# PPG_Foot_Module.net
KiCad netlist of a schematic drawn in EasyEDA
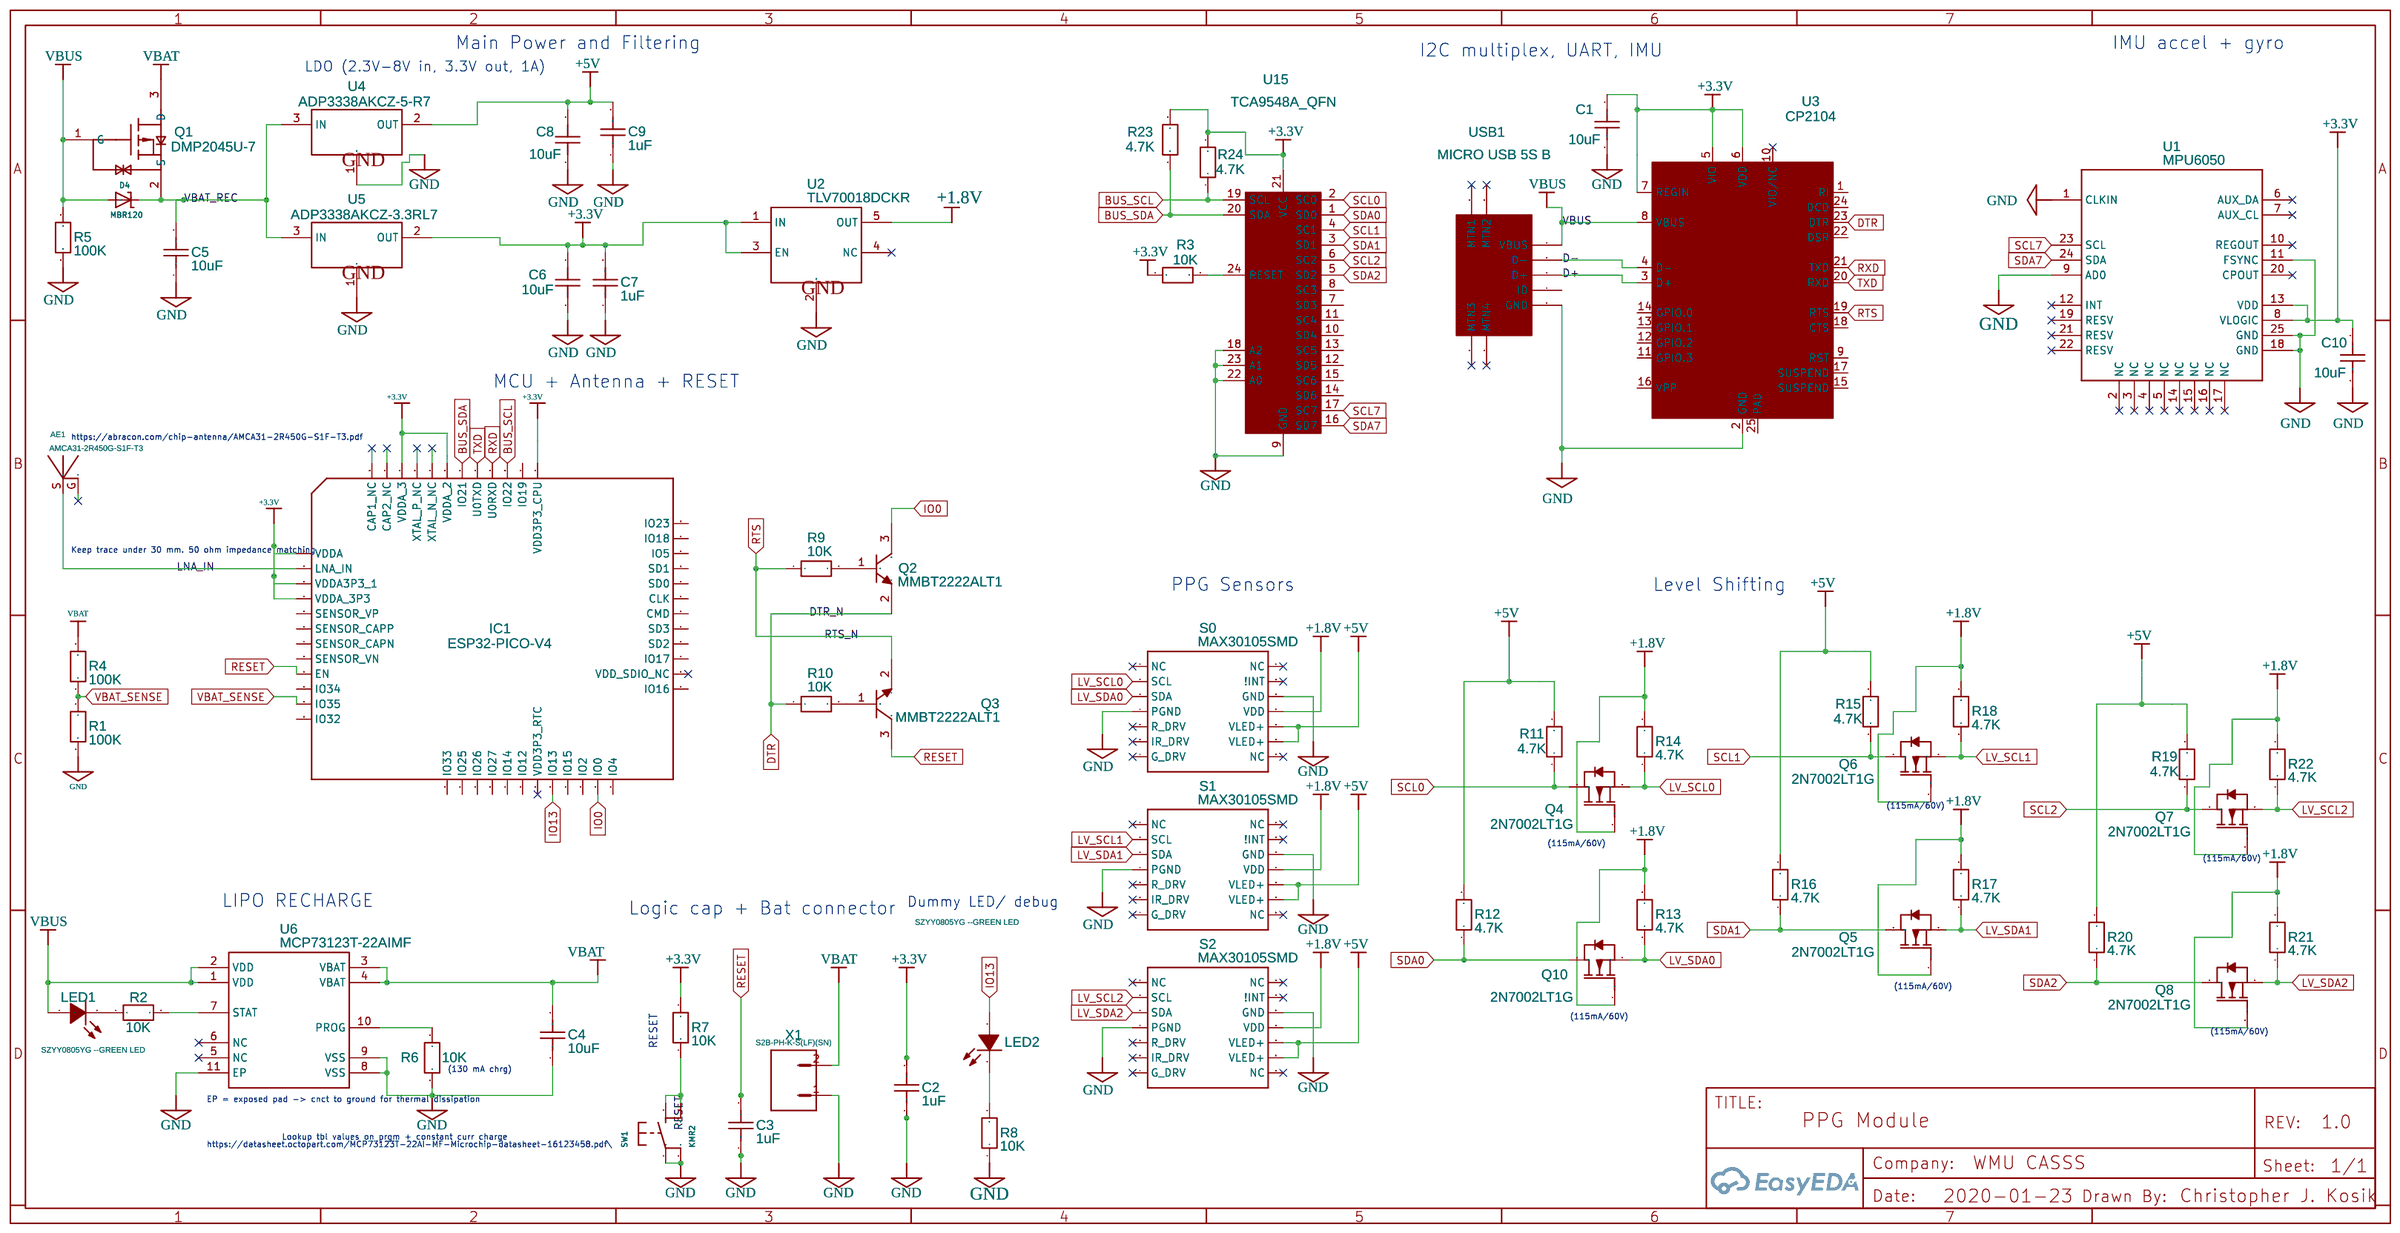
[diagram p0: schematic sheet]

(export (version "E")
  (design (tool "Eeschema 10.0.6"))
  (components
    (comp (ref "AE1")
      (value "AMCA31-2R450G-S1F-T3")
      (fields (field (name "BOM_Supplier Part") "535-14095-1-ND"))
      (libsource (lib "") (part "AMCA31-2R450G-S1F-T3"))
    )
    (comp (ref "C1")
      (value "10uF")
      (fields
        (field (name "BOM_Manufacturer Part") "GJ821BR61E106KE11L")
        (field (name "BOM_Supplier Part") "C471371")
      )
      (libsource (lib "") (part "GJ821BR61E106KE11L_1"))
    )
    (comp (ref "C2")
      (value "1uF")
      (fields
        (field (name "BOM_Manufacturer Part") "C0402X5R105M6R3NT")
        (field (name "BOM_Supplier Part") "C475247")
      )
      (libsource (lib "") (part "C0402X5R105M6R3NT"))
    )
    (comp (ref "C3")
      (value "1uF")
      (fields
        (field (name "BOM_Manufacturer Part") "C0402X5R105M6R3NT")
        (field (name "BOM_Supplier Part") "C475247")
      )
      (libsource (lib "") (part "C0402X5R105M6R3NT"))
    )
    (comp (ref "C4")
      (value "10uF")
      (fields
        (field (name "BOM_Manufacturer Part") "GJ821BR61E106KE11L")
        (field (name "BOM_Supplier Part") "C471371")
      )
      (libsource (lib "") (part "GJ821BR61E106KE11L"))
    )
    (comp (ref "C5")
      (value "10uF")
      (fields
        (field (name "BOM_Manufacturer Part") "GJ821BR61E106KE11L")
        (field (name "BOM_Supplier Part") "C471371")
      )
      (libsource (lib "") (part "GJ821BR61E106KE11L"))
    )
    (comp (ref "C6")
      (value "10uF")
      (fields
        (field (name "BOM_Manufacturer Part") "GJ821BR61E106KE11L")
        (field (name "BOM_Supplier Part") "C471371")
      )
      (libsource (lib "") (part "GJ821BR61E106KE11L_1"))
    )
    (comp (ref "C7")
      (value "1uF")
      (fields
        (field (name "BOM_Manufacturer Part") "C0402X5R105M6R3NT")
        (field (name "BOM_Supplier Part") "C475247")
      )
      (libsource (lib "") (part "C0402X5R105M6R3NT"))
    )
    (comp (ref "C8")
      (value "10uF")
      (fields
        (field (name "BOM_Manufacturer Part") "GJ821BR61E106KE11L")
        (field (name "BOM_Supplier Part") "C471371")
      )
      (libsource (lib "") (part "GJ821BR61E106KE11L"))
    )
    (comp (ref "C9")
      (value "1uF")
      (fields
        (field (name "BOM_Manufacturer Part") "C0402X5R105M6R3NT")
        (field (name "BOM_Supplier Part") "C475247")
      )
      (libsource (lib "") (part "C0402X5R105M6R3NT"))
    )
    (comp (ref "C10")
      (value "10uF")
      (fields
        (field (name "BOM_Manufacturer Part") "GJ821BR61E106KE11L")
        (field (name "BOM_Supplier Part") "C471371")
      )
      (libsource (lib "") (part "GJ821BR61E106KE11L_1"))
    )
    (comp (ref "D4") (value "MBR120") (libsource (lib "") (part "Unknown_75_-680")))
    (comp (ref "IC1") (value "ESP32-PICO-V4") (libsource (lib "") (part "CY8C29666_QFN48")))
    (comp (ref "LED1")
      (value "SZYY0805YG --GREEN LED")
      (fields
        (field (name "BOM_Manufacturer Part") "SZYY0805YG")
        (field (name "BOM_Supplier Part") "C434435")
      )
      (libsource (lib "") (part "SZYY0805YG --GREEN LED"))
    )
    (comp (ref "LED2")
      (value "SZYY0805YG --GREEN LED")
      (fields
        (field (name "BOM_Manufacturer Part") "SZYY0805YG")
        (field (name "BOM_Supplier Part") "C434435")
      )
      (libsource (lib "") (part "SZYY0805YG --GREEN LED_1"))
    )
    (comp (ref "Q1")
      (value "DMP2045U-7")
      (fields (field (name "BOM_Supplier Part") "C146276"))
      (libsource (lib "") (part "DMP2045U-7"))
    )
    (comp (ref "Q2") (value "MMBT2222ALT1") (libsource (lib "") (part "MMBT2222ALT1")))
    (comp (ref "Q3") (value "MMBT2222ALT1") (libsource (lib "") (part "MMBT2222ALT1_1")))
    (comp (ref "Q4")
      (value "2N7002LT1G")
      (fields (field (name "BOM_Supplier Part") "C16338"))
      (libsource (lib "") (part "2N7002LT1G"))
    )
    (comp (ref "Q5")
      (value "2N7002LT1G")
      (fields (field (name "BOM_Supplier Part") "C16338"))
      (libsource (lib "") (part "2N7002LT1G"))
    )
    (comp (ref "Q6")
      (value "2N7002LT1G")
      (fields (field (name "BOM_Supplier Part") "C16338"))
      (libsource (lib "") (part "2N7002LT1G"))
    )
    (comp (ref "Q7")
      (value "2N7002LT1G")
      (fields (field (name "BOM_Supplier Part") "C16338"))
      (libsource (lib "") (part "2N7002LT1G"))
    )
    (comp (ref "Q8")
      (value "2N7002LT1G")
      (fields (field (name "BOM_Supplier Part") "C16338"))
      (libsource (lib "") (part "2N7002LT1G"))
    )
    (comp (ref "Q10")
      (value "2N7002LT1G")
      (fields (field (name "BOM_Supplier Part") "C16338"))
      (libsource (lib "") (part "2N7002LT1G"))
    )
    (comp (ref "R1")
      (value "100K")
      (fields
        (field (name "BOM_Manufacturer Part") "RAT031003FTP")
        (field (name "BOM_Supplier Part") "C304472")
      )
      (libsource (lib "") (part "RAT031003FTP --100K"))
    )
    (comp (ref "R2")
      (value "10K")
      (fields
        (field (name "BOM_Manufacturer Part") "CR-03JA7---10K")
        (field (name "BOM_Supplier Part") "C465463")
      )
      (libsource (lib "") (part "CR-03JA7---10K"))
    )
    (comp (ref "R3")
      (value "10K")
      (fields
        (field (name "BOM_Manufacturer Part") "CR-03JA7---10K")
        (field (name "BOM_Supplier Part") "C465463")
      )
      (libsource (lib "") (part "CR-03JA7---10K"))
    )
    (comp (ref "R4")
      (value "100K")
      (fields
        (field (name "BOM_Manufacturer Part") "RAT031003FTP")
        (field (name "BOM_Supplier Part") "C304472")
      )
      (libsource (lib "") (part "RAT031003FTP --100K"))
    )
    (comp (ref "R5")
      (value "100K")
      (fields
        (field (name "BOM_Manufacturer Part") "RAT031003FTP")
        (field (name "BOM_Supplier Part") "C304472")
      )
      (libsource (lib "") (part "RAT031003FTP --100K"))
    )
    (comp (ref "R6")
      (value "10K")
      (fields
        (field (name "BOM_Manufacturer Part") "CR-03JA7---10K")
        (field (name "BOM_Supplier Part") "C465463")
      )
      (libsource (lib "") (part "CR-03JA7---10K_1"))
    )
    (comp (ref "R7")
      (value "10K")
      (fields
        (field (name "BOM_Manufacturer Part") "CR-03JA7---10K")
        (field (name "BOM_Supplier Part") "C465463")
      )
      (libsource (lib "") (part "CR-03JA7---10K_1"))
    )
    (comp (ref "R8")
      (value "10K")
      (fields
        (field (name "BOM_Manufacturer Part") "CR-03JA7---10K")
        (field (name "BOM_Supplier Part") "C465463")
      )
      (libsource (lib "") (part "CR-03JA7---10K_1"))
    )
    (comp (ref "R9")
      (value "10K")
      (fields
        (field (name "BOM_Manufacturer Part") "CR-03JA7---10K")
        (field (name "BOM_Supplier Part") "C465463")
      )
      (libsource (lib "") (part "CR-03JA7---10K"))
    )
    (comp (ref "R10")
      (value "10K")
      (fields
        (field (name "BOM_Manufacturer Part") "CR-03JA7---10K")
        (field (name "BOM_Supplier Part") "C465463")
      )
      (libsource (lib "") (part "CR-03JA7---10K"))
    )
    (comp (ref "R11")
      (value "4.7K")
      (fields
        (field (name "BOM_Manufacturer Part") "ERJP03J472V")
        (field (name "BOM_Supplier Part") "C427275")
      )
      (libsource (lib "") (part "ERJP03J472V --4.7K"))
    )
    (comp (ref "R12")
      (value "4.7K")
      (fields
        (field (name "BOM_Manufacturer Part") "ERJP03J472V")
        (field (name "BOM_Supplier Part") "C427275")
      )
      (libsource (lib "") (part "ERJP03J472V --4.7K"))
    )
    (comp (ref "R13")
      (value "4.7K")
      (fields
        (field (name "BOM_Manufacturer Part") "ERJP03J472V")
        (field (name "BOM_Supplier Part") "C427275")
      )
      (libsource (lib "") (part "ERJP03J472V --4.7K"))
    )
    (comp (ref "R14")
      (value "4.7K")
      (fields
        (field (name "BOM_Manufacturer Part") "ERJP03J472V")
        (field (name "BOM_Supplier Part") "C427275")
      )
      (libsource (lib "") (part "ERJP03J472V --4.7K"))
    )
    (comp (ref "R15")
      (value "4.7K")
      (fields
        (field (name "BOM_Manufacturer Part") "ERJP03J472V")
        (field (name "BOM_Supplier Part") "C427275")
      )
      (libsource (lib "") (part "ERJP03J472V --4.7K"))
    )
    (comp (ref "R16")
      (value "4.7K")
      (fields
        (field (name "BOM_Manufacturer Part") "ERJP03J472V")
        (field (name "BOM_Supplier Part") "C427275")
      )
      (libsource (lib "") (part "ERJP03J472V --4.7K"))
    )
    (comp (ref "R17")
      (value "4.7K")
      (fields
        (field (name "BOM_Manufacturer Part") "ERJP03J472V")
        (field (name "BOM_Supplier Part") "C427275")
      )
      (libsource (lib "") (part "ERJP03J472V --4.7K"))
    )
    (comp (ref "R18")
      (value "4.7K")
      (fields
        (field (name "BOM_Manufacturer Part") "ERJP03J472V")
        (field (name "BOM_Supplier Part") "C427275")
      )
      (libsource (lib "") (part "ERJP03J472V --4.7K"))
    )
    (comp (ref "R19")
      (value "4.7K")
      (fields
        (field (name "BOM_Manufacturer Part") "ERJP03J472V")
        (field (name "BOM_Supplier Part") "C427275")
      )
      (libsource (lib "") (part "ERJP03J472V --4.7K"))
    )
    (comp (ref "R20")
      (value "4.7K")
      (fields
        (field (name "BOM_Manufacturer Part") "ERJP03J472V")
        (field (name "BOM_Supplier Part") "C427275")
      )
      (libsource (lib "") (part "ERJP03J472V --4.7K"))
    )
    (comp (ref "R21")
      (value "4.7K")
      (fields
        (field (name "BOM_Manufacturer Part") "ERJP03J472V")
        (field (name "BOM_Supplier Part") "C427275")
      )
      (libsource (lib "") (part "ERJP03J472V --4.7K"))
    )
    (comp (ref "R22")
      (value "4.7K")
      (fields
        (field (name "BOM_Manufacturer Part") "ERJP03J472V")
        (field (name "BOM_Supplier Part") "C427275")
      )
      (libsource (lib "") (part "ERJP03J472V --4.7K"))
    )
    (comp (ref "R23")
      (value "4.7K")
      (fields
        (field (name "BOM_Manufacturer Part") "ERJP03J472V")
        (field (name "BOM_Supplier Part") "C427275")
      )
      (libsource (lib "") (part "ERJP03J472V --4.7K"))
    )
    (comp (ref "R24")
      (value "4.7K")
      (fields
        (field (name "BOM_Manufacturer Part") "ERJP03J472V")
        (field (name "BOM_Supplier Part") "C427275")
      )
      (libsource (lib "") (part "ERJP03J472V --4.7K"))
    )
    (comp (ref "S0") (value "MAX30105SMD") (libsource (lib "") (part "MAX30105SMD")))
    (comp (ref "S1") (value "MAX30105SMD") (libsource (lib "") (part "MAX30105SMD")))
    (comp (ref "S2") (value "MAX30105SMD") (libsource (lib "") (part "MAX30105SMD")))
    (comp (ref "SW1") (value "KMR2") (libsource (lib "") (part "Unknown_435_-60")))
    (comp (ref "U1") (value "MPU6050") (libsource (lib "") (part "MPU6050")))
    (comp (ref "U2") (value "TLV70018DCKR") (libsource (lib "") (part "TLV70018DCKR")))
    (comp (ref "U3") (value "CP2104") (libsource (lib "") (part "CP2104")))
    (comp (ref "U4") (value "ADP3338AKCZ-5-R7") (libsource (lib "") (part "ADP3338AKCZ-5-R7")))
    (comp (ref "U5") (value "ADP3338AKCZ-3.3RL7") (libsource (lib "") (part "ADP3338AKCZ-3.3RL7")))
    (comp (ref "U6") (value "MCP73123T-22AIMF") (libsource (lib "") (part "MCP73123T-22AIMF")))
    (comp (ref "U15") (value "TCA9548A_QFN") (libsource (lib "") (part "TCA9548A_QFN")))
    (comp (ref "USB1")
      (value "MICRO USB 5S B")
      (fields
        (field (name "BOM_Manufacturer Part") "micro USBFemale")
        (field (name "BOM_Supplier Part") "C10418")
      )
      (libsource (lib "") (part "MICRO USB 5S B"))
    )
    (comp (ref "X1") (value "S2B-PH-K-S(LF)(SN)") (libsource (lib "") (part "S2B-PH-K-S(LF)(SN)")))
  )
  (nets
    (net (code "1") (name "+1.8V") (class "Default")
      (node (ref "Q10") (pin "1") (pinfunction "G_1") (pintype "unspecified"))
      (node (ref "Q4") (pin "1") (pinfunction "G_1") (pintype "unspecified"))
      (node (ref "Q5") (pin "1") (pinfunction "G_1") (pintype "unspecified"))
      (node (ref "Q6") (pin "1") (pinfunction "G_1") (pintype "unspecified"))
      (node (ref "Q7") (pin "1") (pinfunction "G_1") (pintype "unspecified"))
      (node (ref "Q8") (pin "1") (pinfunction "G_1") (pintype "unspecified"))
      (node (ref "R13") (pin "2") (pinfunction "2_2") (pintype "unspecified"))
      (node (ref "R14") (pin "2") (pinfunction "2_2") (pintype "unspecified"))
      (node (ref "R17") (pin "2") (pinfunction "2_2") (pintype "unspecified"))
      (node (ref "R18") (pin "2") (pinfunction "2_2") (pintype "unspecified"))
      (node (ref "R21") (pin "2") (pinfunction "2_2") (pintype "unspecified"))
      (node (ref "R22") (pin "2") (pinfunction "2_2") (pintype "unspecified"))
      (node (ref "S0") (pin "11") (pinfunction "VDD_11") (pintype "bidirectional"))
      (node (ref "S1") (pin "11") (pinfunction "VDD_11") (pintype "bidirectional"))
      (node (ref "S2") (pin "11") (pinfunction "VDD_11") (pintype "bidirectional"))
      (node (ref "U2") (pin "5") (pinfunction "OUT_5") (pintype "passive"))
    )
    (net (code "2") (name "+3.3V") (class "Default")
      (node (ref "C1") (pin "1") (pinfunction "1_1") (pintype "unspecified"))
      (node (ref "C10") (pin "1") (pinfunction "1_1") (pintype "unspecified"))
      (node (ref "C2") (pin "2") (pinfunction "2_2") (pintype "unspecified"))
      (node (ref "C6") (pin "1") (pinfunction "1_1") (pintype "unspecified"))
      (node (ref "C7") (pin "2") (pinfunction "2_2") (pintype "unspecified"))
      (node (ref "IC1") (pin "1") (pinfunction "VDDA_1") (pintype "bidirectional"))
      (node (ref "IC1") (pin "3") (pinfunction "VDDA3P3_1_3") (pintype "bidirectional"))
      (node (ref "IC1") (pin "37") (pinfunction "VDD3P3_CPU_37") (pintype "bidirectional"))
      (node (ref "IC1") (pin "4") (pinfunction "VDDA_3P3_4") (pintype "bidirectional"))
      (node (ref "IC1") (pin "43") (pinfunction "VDDA_2_43") (pintype "bidirectional"))
      (node (ref "IC1") (pin "46") (pinfunction "VDDA_3_46") (pintype "bidirectional"))
      (node (ref "R23") (pin "2") (pinfunction "2_2") (pintype "unspecified"))
      (node (ref "R24") (pin "2") (pinfunction "2_2") (pintype "unspecified"))
      (node (ref "R3") (pin "1") (pinfunction "1_1") (pintype "unspecified"))
      (node (ref "R7") (pin "2") (pinfunction "2_2") (pintype "unspecified"))
      (node (ref "U1") (pin "13") (pinfunction "VDD_13") (pintype "passive"))
      (node (ref "U1") (pin "8") (pinfunction "VLOGIC_8") (pintype "passive"))
      (node (ref "U15") (pin "21") (pinfunction "VCC_21") (pintype "bidirectional"))
      (node (ref "U2") (pin "1") (pinfunction "IN_1") (pintype "passive"))
      (node (ref "U2") (pin "3") (pinfunction "EN_3") (pintype "unspecified"))
      (node (ref "U3") (pin "5") (pinfunction "VIO_5") (pintype "bidirectional"))
      (node (ref "U3") (pin "6") (pinfunction "VDD_6") (pintype "bidirectional"))
      (node (ref "U3") (pin "7") (pinfunction "REGIN_7") (pintype "bidirectional"))
      (node (ref "U5") (pin "2") (pinfunction "OUT_2") (pintype "passive"))
    )
    (net (code "3") (name "+5V") (class "Default")
      (node (ref "C8") (pin "2") (pinfunction "2_2") (pintype "unspecified"))
      (node (ref "C9") (pin "2") (pinfunction "2_2") (pintype "unspecified"))
      (node (ref "R11") (pin "2") (pinfunction "2_2") (pintype "unspecified"))
      (node (ref "R12") (pin "2") (pinfunction "2_2") (pintype "unspecified"))
      (node (ref "R15") (pin "2") (pinfunction "2_2") (pintype "unspecified"))
      (node (ref "R16") (pin "2") (pinfunction "2_2") (pintype "unspecified"))
      (node (ref "R19") (pin "2") (pinfunction "2_2") (pintype "unspecified"))
      (node (ref "R20") (pin "2") (pinfunction "2_2") (pintype "unspecified"))
      (node (ref "S0") (pin "10") (pinfunction "VLED+_10") (pintype "bidirectional"))
      (node (ref "S0") (pin "9") (pinfunction "VLED+_9") (pintype "bidirectional"))
      (node (ref "S1") (pin "10") (pinfunction "VLED+_10") (pintype "bidirectional"))
      (node (ref "S1") (pin "9") (pinfunction "VLED+_9") (pintype "bidirectional"))
      (node (ref "S2") (pin "10") (pinfunction "VLED+_10") (pintype "bidirectional"))
      (node (ref "S2") (pin "9") (pinfunction "VLED+_9") (pintype "bidirectional"))
      (node (ref "U4") (pin "2") (pinfunction "OUT_2") (pintype "passive"))
    )
    (net (code "4") (name "/D+") (class "Default")
      (node (ref "U3") (pin "3") (pinfunction "D+_3") (pintype "bidirectional"))
      (node (ref "USB1") (pin "3") (pinfunction "D+_3") (pintype "input"))
    )
    (net (code "5") (name "/D-") (class "Default")
      (node (ref "U3") (pin "4") (pinfunction "D-_4") (pintype "bidirectional"))
      (node (ref "USB1") (pin "2") (pinfunction "D-_2") (pintype "input"))
    )
    (net (code "6") (name "/LNA_IN") (class "Default")
      (node (ref "AE1") (pin "S") (pinfunction "S_S") (pintype "unspecified"))
      (node (ref "IC1") (pin "2") (pinfunction "LNA_IN_2") (pintype "bidirectional"))
    )
    (net (code "7") (name "/VBAT_REC") (class "Default")
      (node (ref "C5") (pin "2") (pinfunction "2_2") (pintype "unspecified"))
      (node (ref "D4") (pin "2") (pinfunction "C_2") (pintype "bidirectional"))
      (node (ref "Q1") (pin "2") (pinfunction "S_2") (pintype "unspecified"))
      (node (ref "U4") (pin "3") (pinfunction "IN_3") (pintype "passive"))
      (node (ref "U5") (pin "3") (pinfunction "IN_3") (pintype "passive"))
    )
    (net (code "8") (name "BUS_SCL") (class "Default")
      (node (ref "IC1") (pin "39") (pinfunction "IO22_39") (pintype "bidirectional"))
      (node (ref "R24") (pin "1") (pinfunction "1_1") (pintype "unspecified"))
      (node (ref "U15") (pin "19") (pinfunction "SCL_19") (pintype "bidirectional"))
    )
    (net (code "9") (name "BUS_SDA") (class "Default")
      (node (ref "IC1") (pin "42") (pinfunction "IO21_42") (pintype "bidirectional"))
      (node (ref "R23") (pin "1") (pinfunction "1_1") (pintype "unspecified"))
      (node (ref "U15") (pin "20") (pinfunction "SDA_20") (pintype "bidirectional"))
    )
    (net (code "10") (name "DTR") (class "Default")
      (node (ref "Q2") (pin "2") (pinfunction "E_2") (pintype "unspecified"))
      (node (ref "R10") (pin "1") (pinfunction "1_1") (pintype "unspecified"))
      (node (ref "U3") (pin "23") (pinfunction "DTR_23") (pintype "output"))
    )
    (net (code "11") (name "GND") (class "Default")
      (node (ref "C1") (pin "2") (pinfunction "2_2") (pintype "unspecified"))
      (node (ref "C10") (pin "2") (pinfunction "2_2") (pintype "unspecified"))
      (node (ref "C2") (pin "1") (pinfunction "1_1") (pintype "unspecified"))
      (node (ref "C3") (pin "1") (pinfunction "1_1") (pintype "unspecified"))
      (node (ref "C4") (pin "1") (pinfunction "1_1") (pintype "unspecified"))
      (node (ref "C5") (pin "1") (pinfunction "1_1") (pintype "unspecified"))
      (node (ref "C6") (pin "2") (pinfunction "2_2") (pintype "unspecified"))
      (node (ref "C7") (pin "1") (pinfunction "1_1") (pintype "unspecified"))
      (node (ref "C8") (pin "1") (pinfunction "1_1") (pintype "unspecified"))
      (node (ref "C9") (pin "1") (pinfunction "1_1") (pintype "unspecified"))
      (node (ref "R1") (pin "1") (pinfunction "1_1") (pintype "unspecified"))
      (node (ref "R5") (pin "1") (pinfunction "1_1") (pintype "unspecified"))
      (node (ref "R6") (pin "1") (pinfunction "1_1") (pintype "unspecified"))
      (node (ref "R8") (pin "1") (pinfunction "1_1") (pintype "unspecified"))
      (node (ref "S0") (pin "12") (pinfunction "GND_12") (pintype "bidirectional"))
      (node (ref "S0") (pin "4") (pinfunction "PGND_4") (pintype "bidirectional"))
      (node (ref "S1") (pin "12") (pinfunction "GND_12") (pintype "bidirectional"))
      (node (ref "S1") (pin "4") (pinfunction "PGND_4") (pintype "bidirectional"))
      (node (ref "S2") (pin "12") (pinfunction "GND_12") (pintype "bidirectional"))
      (node (ref "S2") (pin "4") (pinfunction "PGND_4") (pintype "bidirectional"))
      (node (ref "SW1") (pin "A") (pinfunction "P_A") (pintype "bidirectional"))
      (node (ref "SW1") (pin "A'") (pinfunction "P1_A'") (pintype "bidirectional"))
      (node (ref "U1") (pin "1") (pinfunction "CLKIN_1") (pintype "input"))
      (node (ref "U1") (pin "11") (pinfunction "FSYNC_11") (pintype "input"))
      (node (ref "U1") (pin "18") (pinfunction "GND_18") (pintype "passive"))
      (node (ref "U1") (pin "25") (pinfunction "GND_25") (pintype "passive"))
      (node (ref "U1") (pin "9") (pinfunction "AD0_9") (pintype "input"))
      (node (ref "U15") (pin "18") (pinfunction "A2_18") (pintype "input"))
      (node (ref "U15") (pin "22") (pinfunction "A0_22") (pintype "input"))
      (node (ref "U15") (pin "23") (pinfunction "A1_23") (pintype "input"))
      (node (ref "U15") (pin "9") (pinfunction "GND_9") (pintype "bidirectional"))
      (node (ref "U2") (pin "2") (pinfunction "GND_2") (pintype "passive"))
      (node (ref "U3") (pin "2") (pinfunction "GND_2") (pintype "bidirectional"))
      (node (ref "U4") (pin "1") (pinfunction "GND_1") (pintype "passive"))
      (node (ref "U5") (pin "1") (pinfunction "GND_1") (pintype "passive"))
      (node (ref "U6") (pin "11") (pinfunction "EP_11") (pintype "passive"))
      (node (ref "U6") (pin "8") (pinfunction "VSS_8") (pintype "passive"))
      (node (ref "U6") (pin "9") (pinfunction "VSS_9") (pintype "passive"))
      (node (ref "USB1") (pin "5") (pinfunction "GND_5") (pintype "input"))
      (node (ref "X1") (pin "1") (pinfunction "1_1") (pintype "unspecified"))
    )
    (net (code "12") (name "IO0") (class "Default")
      (node (ref "IC1") (pin "23") (pinfunction "IO0_23") (pintype "bidirectional"))
      (node (ref "Q2") (pin "3") (pinfunction "C_3") (pintype "unspecified"))
    )
    (net (code "13") (name "IO13") (class "Default")
      (node (ref "IC1") (pin "20") (pinfunction "IO13_20") (pintype "bidirectional"))
      (node (ref "LED2") (pin "1") (pinfunction "+_1") (pintype "unspecified"))
    )
    (net (code "14") (name "LV_SCL0") (class "Default")
      (node (ref "Q4") (pin "2") (pinfunction "S_2") (pintype "unspecified"))
      (node (ref "R14") (pin "1") (pinfunction "1_1") (pintype "unspecified"))
      (node (ref "S0") (pin "2") (pinfunction "SCL_2") (pintype "bidirectional"))
    )
    (net (code "15") (name "LV_SCL1") (class "Default")
      (node (ref "Q6") (pin "2") (pinfunction "S_2") (pintype "unspecified"))
      (node (ref "R18") (pin "1") (pinfunction "1_1") (pintype "unspecified"))
      (node (ref "S1") (pin "2") (pinfunction "SCL_2") (pintype "bidirectional"))
    )
    (net (code "16") (name "LV_SCL2") (class "Default")
      (node (ref "Q7") (pin "2") (pinfunction "S_2") (pintype "unspecified"))
      (node (ref "R22") (pin "1") (pinfunction "1_1") (pintype "unspecified"))
      (node (ref "S2") (pin "2") (pinfunction "SCL_2") (pintype "bidirectional"))
    )
    (net (code "17") (name "LV_SDA0") (class "Default")
      (node (ref "Q10") (pin "2") (pinfunction "S_2") (pintype "unspecified"))
      (node (ref "R13") (pin "1") (pinfunction "1_1") (pintype "unspecified"))
      (node (ref "S0") (pin "3") (pinfunction "SDA_3") (pintype "bidirectional"))
    )
    (net (code "18") (name "LV_SDA1") (class "Default")
      (node (ref "Q5") (pin "2") (pinfunction "S_2") (pintype "unspecified"))
      (node (ref "R17") (pin "1") (pinfunction "1_1") (pintype "unspecified"))
      (node (ref "S1") (pin "3") (pinfunction "SDA_3") (pintype "bidirectional"))
    )
    (net (code "19") (name "LV_SDA2") (class "Default")
      (node (ref "Q8") (pin "2") (pinfunction "S_2") (pintype "unspecified"))
      (node (ref "R21") (pin "1") (pinfunction "1_1") (pintype "unspecified"))
      (node (ref "S2") (pin "3") (pinfunction "SDA_3") (pintype "bidirectional"))
    )
    (net (code "20") (name "Net-(LED1--)") (class "Default")
      (node (ref "LED1") (pin "2") (pinfunction "-_2") (pintype "unspecified"))
      (node (ref "R2") (pin "1") (pinfunction "1_1") (pintype "unspecified"))
    )
    (net (code "21") (name "Net-(LED2--)") (class "Default")
      (node (ref "LED2") (pin "2") (pinfunction "-_2") (pintype "unspecified"))
      (node (ref "R8") (pin "2") (pinfunction "2_2") (pintype "unspecified"))
    )
    (net (code "22") (name "Net-(Q2-B)") (class "Default")
      (node (ref "Q2") (pin "1") (pinfunction "B_1") (pintype "unspecified"))
      (node (ref "R9") (pin "2") (pinfunction "2_2") (pintype "unspecified"))
    )
    (net (code "23") (name "Net-(Q3-B)") (class "Default")
      (node (ref "Q3") (pin "1") (pinfunction "B_1") (pintype "unspecified"))
      (node (ref "R10") (pin "2") (pinfunction "2_2") (pintype "unspecified"))
    )
    (net (code "24") (name "Net-(U6-PROG)") (class "Default")
      (node (ref "R6") (pin "2") (pinfunction "2_2") (pintype "unspecified"))
      (node (ref "U6") (pin "10") (pinfunction "PROG_10") (pintype "unspecified"))
    )
    (net (code "25") (name "Net-(U6-STAT)") (class "Default")
      (node (ref "R2") (pin "2") (pinfunction "2_2") (pintype "unspecified"))
      (node (ref "U6") (pin "7") (pinfunction "STAT_7") (pintype "unspecified"))
    )
    (net (code "26") (name "Net-(U15-RESET)") (class "Default")
      (node (ref "R3") (pin "2") (pinfunction "2_2") (pintype "unspecified"))
      (node (ref "U15") (pin "24") (pinfunction "RESET_24") (pintype "input"))
    )
    (net (code "27") (name "RESET") (class "Default")
      (node (ref "C3") (pin "2") (pinfunction "2_2") (pintype "unspecified"))
      (node (ref "IC1") (pin "9") (pinfunction "EN_9") (pintype "bidirectional"))
      (node (ref "Q3") (pin "3") (pinfunction "C_3") (pintype "unspecified"))
      (node (ref "R7") (pin "1") (pinfunction "1_1") (pintype "unspecified"))
      (node (ref "SW1") (pin "B") (pinfunction "S_B") (pintype "bidirectional"))
      (node (ref "SW1") (pin "B'") (pinfunction "S1_B'") (pintype "bidirectional"))
    )
    (net (code "28") (name "RTS") (class "Default")
      (node (ref "Q3") (pin "2") (pinfunction "E_2") (pintype "unspecified"))
      (node (ref "R9") (pin "1") (pinfunction "1_1") (pintype "unspecified"))
      (node (ref "U3") (pin "19") (pinfunction "RTS_19") (pintype "output"))
    )
    (net (code "29") (name "RXD") (class "Default")
      (node (ref "IC1") (pin "40") (pinfunction "U0RXD_40") (pintype "bidirectional"))
      (node (ref "U3") (pin "21") (pinfunction "TXD_21") (pintype "output"))
    )
    (net (code "30") (name "SCL0") (class "Default")
      (node (ref "Q4") (pin "3") (pinfunction "D_3") (pintype "unspecified"))
      (node (ref "R11") (pin "1") (pinfunction "1_1") (pintype "unspecified"))
      (node (ref "U15") (pin "2") (pinfunction "SC0_2") (pintype "bidirectional"))
    )
    (net (code "31") (name "SCL1") (class "Default")
      (node (ref "Q6") (pin "3") (pinfunction "D_3") (pintype "unspecified"))
      (node (ref "R15") (pin "1") (pinfunction "1_1") (pintype "unspecified"))
      (node (ref "U15") (pin "4") (pinfunction "SC1_4") (pintype "bidirectional"))
    )
    (net (code "32") (name "SCL2") (class "Default")
      (node (ref "Q7") (pin "3") (pinfunction "D_3") (pintype "unspecified"))
      (node (ref "R19") (pin "1") (pinfunction "1_1") (pintype "unspecified"))
      (node (ref "U15") (pin "6") (pinfunction "SC2_6") (pintype "bidirectional"))
    )
    (net (code "33") (name "SCL7") (class "Default")
      (node (ref "U1") (pin "23") (pinfunction "SCL_23") (pintype "input"))
      (node (ref "U15") (pin "17") (pinfunction "SC7_17") (pintype "bidirectional"))
    )
    (net (code "34") (name "SDA0") (class "Default")
      (node (ref "Q10") (pin "3") (pinfunction "D_3") (pintype "unspecified"))
      (node (ref "R12") (pin "1") (pinfunction "1_1") (pintype "unspecified"))
      (node (ref "U15") (pin "1") (pinfunction "SD0_1") (pintype "bidirectional"))
    )
    (net (code "35") (name "SDA1") (class "Default")
      (node (ref "Q5") (pin "3") (pinfunction "D_3") (pintype "unspecified"))
      (node (ref "R16") (pin "1") (pinfunction "1_1") (pintype "unspecified"))
      (node (ref "U15") (pin "3") (pinfunction "SD1_3") (pintype "bidirectional"))
    )
    (net (code "36") (name "SDA2") (class "Default")
      (node (ref "Q8") (pin "3") (pinfunction "D_3") (pintype "unspecified"))
      (node (ref "R20") (pin "1") (pinfunction "1_1") (pintype "unspecified"))
      (node (ref "U15") (pin "5") (pinfunction "SD2_5") (pintype "bidirectional"))
    )
    (net (code "37") (name "SDA7") (class "Default")
      (node (ref "U1") (pin "24") (pinfunction "SDA_24") (pintype "unspecified"))
      (node (ref "U15") (pin "16") (pinfunction "SD7_16") (pintype "bidirectional"))
    )
    (net (code "38") (name "TXD") (class "Default")
      (node (ref "IC1") (pin "41") (pinfunction "U0TXD_41") (pintype "bidirectional"))
      (node (ref "U3") (pin "20") (pinfunction "RXD_20") (pintype "input"))
    )
    (net (code "39") (name "VBAT") (class "Default")
      (node (ref "C4") (pin "2") (pinfunction "2_2") (pintype "unspecified"))
      (node (ref "Q1") (pin "3") (pinfunction "D_3") (pintype "unspecified"))
      (node (ref "R4") (pin "2") (pinfunction "2_2") (pintype "unspecified"))
      (node (ref "U6") (pin "3") (pinfunction "VBAT_3") (pintype "passive"))
      (node (ref "U6") (pin "4") (pinfunction "VBAT_4") (pintype "passive"))
      (node (ref "X1") (pin "2") (pinfunction "2_2") (pintype "unspecified"))
    )
    (net (code "40") (name "VBAT_SENSE") (class "Default")
      (node (ref "IC1") (pin "11") (pinfunction "IO35_11") (pintype "bidirectional"))
      (node (ref "R1") (pin "2") (pinfunction "2_2") (pintype "unspecified"))
      (node (ref "R4") (pin "1") (pinfunction "1_1") (pintype "unspecified"))
    )
    (net (code "41") (name "VBUS") (class "Default")
      (node (ref "D4") (pin "1") (pinfunction "A_1") (pintype "bidirectional"))
      (node (ref "LED1") (pin "1") (pinfunction "+_1") (pintype "unspecified"))
      (node (ref "Q1") (pin "1") (pinfunction "G_1") (pintype "unspecified"))
      (node (ref "R5") (pin "2") (pinfunction "2_2") (pintype "unspecified"))
      (node (ref "U3") (pin "8") (pinfunction "VBUS_8") (pintype "input"))
      (node (ref "U6") (pin "1") (pinfunction "VDD_1") (pintype "passive"))
      (node (ref "U6") (pin "2") (pinfunction "VDD_2") (pintype "passive"))
      (node (ref "USB1") (pin "1") (pinfunction "VBUS_1") (pintype "input"))
    )
    (net (code "42") (name "unconnected-(AE1-PadG)") (class "Default")
      (node (ref "AE1") (pin "G") (pinfunction "G_G") (pintype "unspecified+no_connect"))
    )
    (net (code "43") (name "unconnected-(IC1-CAP1_NC-Pad48)") (class "Default")
      (node (ref "IC1") (pin "48") (pinfunction "CAP1_NC_48") (pintype "bidirectional+no_connect"))
    )
    (net (code "44") (name "unconnected-(IC1-CAP2_NC-Pad47)") (class "Default")
      (node (ref "IC1") (pin "47") (pinfunction "CAP2_NC_47") (pintype "bidirectional+no_connect"))
    )
    (net (code "45") (name "unconnected-(IC1-CLK-Pad31)") (class "Default")
      (node (ref "IC1") (pin "31") (pinfunction "CLK_31") (pintype "bidirectional"))
    )
    (net (code "46") (name "unconnected-(IC1-CMD-Pad30)") (class "Default")
      (node (ref "IC1") (pin "30") (pinfunction "CMD_30") (pintype "bidirectional"))
    )
    (net (code "47") (name "unconnected-(IC1-IO2-Pad22)") (class "Default")
      (node (ref "IC1") (pin "22") (pinfunction "IO2_22") (pintype "bidirectional"))
    )
    (net (code "48") (name "unconnected-(IC1-IO4-Pad24)") (class "Default")
      (node (ref "IC1") (pin "24") (pinfunction "IO4_24") (pintype "bidirectional"))
    )
    (net (code "49") (name "unconnected-(IC1-IO5-Pad34)") (class "Default")
      (node (ref "IC1") (pin "34") (pinfunction "IO5_34") (pintype "bidirectional"))
    )
    (net (code "50") (name "unconnected-(IC1-IO12-Pad18)") (class "Default")
      (node (ref "IC1") (pin "18") (pinfunction "IO12_18") (pintype "bidirectional"))
    )
    (net (code "51") (name "unconnected-(IC1-IO14-Pad17)") (class "Default")
      (node (ref "IC1") (pin "17") (pinfunction "IO14_17") (pintype "bidirectional"))
    )
    (net (code "52") (name "unconnected-(IC1-IO15-Pad21)") (class "Default")
      (node (ref "IC1") (pin "21") (pinfunction "IO15_21") (pintype "bidirectional"))
    )
    (net (code "53") (name "unconnected-(IC1-IO16-Pad25)") (class "Default")
      (node (ref "IC1") (pin "25") (pinfunction "IO16_25") (pintype "bidirectional"))
    )
    (net (code "54") (name "unconnected-(IC1-IO17-Pad27)") (class "Default")
      (node (ref "IC1") (pin "27") (pinfunction "IO17_27") (pintype "bidirectional"))
    )
    (net (code "55") (name "unconnected-(IC1-IO18-Pad35)") (class "Default")
      (node (ref "IC1") (pin "35") (pinfunction "IO18_35") (pintype "bidirectional"))
    )
    (net (code "56") (name "unconnected-(IC1-IO19-Pad38)") (class "Default")
      (node (ref "IC1") (pin "38") (pinfunction "IO19_38") (pintype "bidirectional"))
    )
    (net (code "57") (name "unconnected-(IC1-IO23-Pad36)") (class "Default")
      (node (ref "IC1") (pin "36") (pinfunction "IO23_36") (pintype "bidirectional"))
    )
    (net (code "58") (name "unconnected-(IC1-IO25-Pad14)") (class "Default")
      (node (ref "IC1") (pin "14") (pinfunction "IO25_14") (pintype "bidirectional"))
    )
    (net (code "59") (name "unconnected-(IC1-IO26-Pad15)") (class "Default")
      (node (ref "IC1") (pin "15") (pinfunction "IO26_15") (pintype "bidirectional"))
    )
    (net (code "60") (name "unconnected-(IC1-IO27-Pad16)") (class "Default")
      (node (ref "IC1") (pin "16") (pinfunction "IO27_16") (pintype "bidirectional"))
    )
    (net (code "61") (name "unconnected-(IC1-IO32-Pad12)") (class "Default")
      (node (ref "IC1") (pin "12") (pinfunction "IO32_12") (pintype "bidirectional"))
    )
    (net (code "62") (name "unconnected-(IC1-IO33-Pad13)") (class "Default")
      (node (ref "IC1") (pin "13") (pinfunction "IO33_13") (pintype "bidirectional"))
    )
    (net (code "63") (name "unconnected-(IC1-IO34-Pad10)") (class "Default")
      (node (ref "IC1") (pin "10") (pinfunction "IO34_10") (pintype "bidirectional"))
    )
    (net (code "64") (name "unconnected-(IC1-SD0-Pad32)") (class "Default")
      (node (ref "IC1") (pin "32") (pinfunction "SD0_32") (pintype "bidirectional"))
    )
    (net (code "65") (name "unconnected-(IC1-SD1-Pad33)") (class "Default")
      (node (ref "IC1") (pin "33") (pinfunction "SD1_33") (pintype "bidirectional"))
    )
    (net (code "66") (name "unconnected-(IC1-SD2-Pad28)") (class "Default")
      (node (ref "IC1") (pin "28") (pinfunction "SD2_28") (pintype "bidirectional"))
    )
    (net (code "67") (name "unconnected-(IC1-SD3-Pad29)") (class "Default")
      (node (ref "IC1") (pin "29") (pinfunction "SD3_29") (pintype "bidirectional"))
    )
    (net (code "68") (name "unconnected-(IC1-SENSOR_CAPN-Pad7)") (class "Default")
      (node (ref "IC1") (pin "7") (pinfunction "SENSOR_CAPN_7") (pintype "bidirectional"))
    )
    (net (code "69") (name "unconnected-(IC1-SENSOR_CAPP-Pad6)") (class "Default")
      (node (ref "IC1") (pin "6") (pinfunction "SENSOR_CAPP_6") (pintype "bidirectional"))
    )
    (net (code "70") (name "unconnected-(IC1-SENSOR_VN-Pad8)") (class "Default")
      (node (ref "IC1") (pin "8") (pinfunction "SENSOR_VN_8") (pintype "bidirectional"))
    )
    (net (code "71") (name "unconnected-(IC1-SENSOR_VP-Pad5)") (class "Default")
      (node (ref "IC1") (pin "5") (pinfunction "SENSOR_VP_5") (pintype "bidirectional"))
    )
    (net (code "72") (name "unconnected-(IC1-VDD3P3_RTC-Pad19)") (class "Default")
      (node (ref "IC1") (pin "19") (pinfunction "VDD3P3_RTC_19") (pintype "bidirectional+no_connect"))
    )
    (net (code "73") (name "unconnected-(IC1-VDD_SDIO_NC-Pad26)") (class "Default")
      (node (ref "IC1") (pin "26") (pinfunction "VDD_SDIO_NC_26") (pintype "bidirectional+no_connect"))
    )
    (net (code "74") (name "unconnected-(IC1-XTAL_N_NC-Pad44)") (class "Default")
      (node (ref "IC1") (pin "44") (pinfunction "XTAL_N_NC_44") (pintype "bidirectional+no_connect"))
    )
    (net (code "75") (name "unconnected-(IC1-XTAL_P_NC-Pad45)") (class "Default")
      (node (ref "IC1") (pin "45") (pinfunction "XTAL_P_NC_45") (pintype "bidirectional+no_connect"))
    )
    (net (code "76") (name "unconnected-(S0-!INT-Pad13)") (class "Default")
      (node (ref "S0") (pin "13") (pinfunction "!INT_13") (pintype "bidirectional+no_connect"))
    )
    (net (code "77") (name "unconnected-(S0-G_DRV-Pad7)") (class "Default")
      (node (ref "S0") (pin "7") (pinfunction "G_DRV_7") (pintype "bidirectional+no_connect"))
    )
    (net (code "78") (name "unconnected-(S0-IR_DRV-Pad6)") (class "Default")
      (node (ref "S0") (pin "6") (pinfunction "IR_DRV_6") (pintype "bidirectional+no_connect"))
    )
    (net (code "79") (name "unconnected-(S0-NC-Pad1)") (class "Default")
      (node (ref "S0") (pin "1") (pinfunction "NC_1") (pintype "bidirectional+no_connect"))
    )
    (net (code "80") (name "unconnected-(S0-NC-Pad8)") (class "Default")
      (node (ref "S0") (pin "8") (pinfunction "NC_8") (pintype "bidirectional+no_connect"))
    )
    (net (code "81") (name "unconnected-(S0-NC-Pad14)") (class "Default")
      (node (ref "S0") (pin "14") (pinfunction "NC_14") (pintype "bidirectional+no_connect"))
    )
    (net (code "82") (name "unconnected-(S0-R_DRV-Pad5)") (class "Default")
      (node (ref "S0") (pin "5") (pinfunction "R_DRV_5") (pintype "bidirectional+no_connect"))
    )
    (net (code "83") (name "unconnected-(S1-!INT-Pad13)") (class "Default")
      (node (ref "S1") (pin "13") (pinfunction "!INT_13") (pintype "bidirectional+no_connect"))
    )
    (net (code "84") (name "unconnected-(S1-G_DRV-Pad7)") (class "Default")
      (node (ref "S1") (pin "7") (pinfunction "G_DRV_7") (pintype "bidirectional+no_connect"))
    )
    (net (code "85") (name "unconnected-(S1-IR_DRV-Pad6)") (class "Default")
      (node (ref "S1") (pin "6") (pinfunction "IR_DRV_6") (pintype "bidirectional+no_connect"))
    )
    (net (code "86") (name "unconnected-(S1-NC-Pad1)") (class "Default")
      (node (ref "S1") (pin "1") (pinfunction "NC_1") (pintype "bidirectional+no_connect"))
    )
    (net (code "87") (name "unconnected-(S1-NC-Pad8)") (class "Default")
      (node (ref "S1") (pin "8") (pinfunction "NC_8") (pintype "bidirectional+no_connect"))
    )
    (net (code "88") (name "unconnected-(S1-NC-Pad14)") (class "Default")
      (node (ref "S1") (pin "14") (pinfunction "NC_14") (pintype "bidirectional+no_connect"))
    )
    (net (code "89") (name "unconnected-(S1-R_DRV-Pad5)") (class "Default")
      (node (ref "S1") (pin "5") (pinfunction "R_DRV_5") (pintype "bidirectional+no_connect"))
    )
    (net (code "90") (name "unconnected-(S2-!INT-Pad13)") (class "Default")
      (node (ref "S2") (pin "13") (pinfunction "!INT_13") (pintype "bidirectional+no_connect"))
    )
    (net (code "91") (name "unconnected-(S2-G_DRV-Pad7)") (class "Default")
      (node (ref "S2") (pin "7") (pinfunction "G_DRV_7") (pintype "bidirectional+no_connect"))
    )
    (net (code "92") (name "unconnected-(S2-IR_DRV-Pad6)") (class "Default")
      (node (ref "S2") (pin "6") (pinfunction "IR_DRV_6") (pintype "bidirectional+no_connect"))
    )
    (net (code "93") (name "unconnected-(S2-NC-Pad1)") (class "Default")
      (node (ref "S2") (pin "1") (pinfunction "NC_1") (pintype "bidirectional+no_connect"))
    )
    (net (code "94") (name "unconnected-(S2-NC-Pad8)") (class "Default")
      (node (ref "S2") (pin "8") (pinfunction "NC_8") (pintype "bidirectional+no_connect"))
    )
    (net (code "95") (name "unconnected-(S2-NC-Pad14)") (class "Default")
      (node (ref "S2") (pin "14") (pinfunction "NC_14") (pintype "bidirectional+no_connect"))
    )
    (net (code "96") (name "unconnected-(S2-R_DRV-Pad5)") (class "Default")
      (node (ref "S2") (pin "5") (pinfunction "R_DRV_5") (pintype "bidirectional+no_connect"))
    )
    (net (code "97") (name "unconnected-(U1-AUX_CL-Pad7)") (class "Default")
      (node (ref "U1") (pin "7") (pinfunction "AUX_CL_7") (pintype "unspecified+no_connect"))
    )
    (net (code "98") (name "unconnected-(U1-AUX_DA-Pad6)") (class "Default")
      (node (ref "U1") (pin "6") (pinfunction "AUX_DA_6") (pintype "unspecified+no_connect"))
    )
    (net (code "99") (name "unconnected-(U1-CPOUT-Pad20)") (class "Default")
      (node (ref "U1") (pin "20") (pinfunction "CPOUT_20") (pintype "output+no_connect"))
    )
    (net (code "100") (name "unconnected-(U1-INT-Pad12)") (class "Default")
      (node (ref "U1") (pin "12") (pinfunction "INT_12") (pintype "unspecified+no_connect"))
    )
    (net (code "101") (name "unconnected-(U1-NC-Pad2)") (class "Default")
      (node (ref "U1") (pin "2") (pinfunction "NC_2") (pintype "unspecified+no_connect"))
    )
    (net (code "102") (name "unconnected-(U1-NC-Pad3)") (class "Default")
      (node (ref "U1") (pin "3") (pinfunction "NC_3") (pintype "unspecified+no_connect"))
    )
    (net (code "103") (name "unconnected-(U1-NC-Pad4)") (class "Default")
      (node (ref "U1") (pin "4") (pinfunction "NC_4") (pintype "unspecified+no_connect"))
    )
    (net (code "104") (name "unconnected-(U1-NC-Pad5)") (class "Default")
      (node (ref "U1") (pin "5") (pinfunction "NC_5") (pintype "unspecified+no_connect"))
    )
    (net (code "105") (name "unconnected-(U1-NC-Pad14)") (class "Default")
      (node (ref "U1") (pin "14") (pinfunction "NC_14") (pintype "unspecified+no_connect"))
    )
    (net (code "106") (name "unconnected-(U1-NC-Pad15)") (class "Default")
      (node (ref "U1") (pin "15") (pinfunction "NC_15") (pintype "unspecified+no_connect"))
    )
    (net (code "107") (name "unconnected-(U1-NC-Pad16)") (class "Default")
      (node (ref "U1") (pin "16") (pinfunction "NC_16") (pintype "unspecified+no_connect"))
    )
    (net (code "108") (name "unconnected-(U1-NC-Pad17)") (class "Default")
      (node (ref "U1") (pin "17") (pinfunction "NC_17") (pintype "unspecified+no_connect"))
    )
    (net (code "109") (name "unconnected-(U1-REGOUT-Pad10)") (class "Default")
      (node (ref "U1") (pin "10") (pinfunction "REGOUT_10") (pintype "output+no_connect"))
    )
    (net (code "110") (name "unconnected-(U1-RESV-Pad19)") (class "Default")
      (node (ref "U1") (pin "19") (pinfunction "RESV_19") (pintype "unspecified+no_connect"))
    )
    (net (code "111") (name "unconnected-(U1-RESV-Pad21)") (class "Default")
      (node (ref "U1") (pin "21") (pinfunction "RESV_21") (pintype "unspecified+no_connect"))
    )
    (net (code "112") (name "unconnected-(U1-RESV-Pad22)") (class "Default")
      (node (ref "U1") (pin "22") (pinfunction "RESV_22") (pintype "unspecified+no_connect"))
    )
    (net (code "113") (name "unconnected-(U2-NC-Pad4)") (class "Default")
      (node (ref "U2") (pin "4") (pinfunction "NC_4") (pintype "unspecified+no_connect"))
    )
    (net (code "114") (name "unconnected-(U3-CTS-Pad18)") (class "Default")
      (node (ref "U3") (pin "18") (pinfunction "CTS_18") (pintype "input"))
    )
    (net (code "115") (name "unconnected-(U3-DCD-Pad24)") (class "Default")
      (node (ref "U3") (pin "24") (pinfunction "DCD_24") (pintype "input"))
    )
    (net (code "116") (name "unconnected-(U3-DSR-Pad22)") (class "Default")
      (node (ref "U3") (pin "22") (pinfunction "DSR_22") (pintype "input"))
    )
    (net (code "117") (name "unconnected-(U3-GPIO.0-Pad14)") (class "Default")
      (node (ref "U3") (pin "14") (pinfunction "GPIO.0_14") (pintype "bidirectional"))
    )
    (net (code "118") (name "unconnected-(U3-GPIO.1-Pad13)") (class "Default")
      (node (ref "U3") (pin "13") (pinfunction "GPIO.1_13") (pintype "bidirectional"))
    )
    (net (code "119") (name "unconnected-(U3-GPIO.2-Pad12)") (class "Default")
      (node (ref "U3") (pin "12") (pinfunction "GPIO.2_12") (pintype "bidirectional"))
    )
    (net (code "120") (name "unconnected-(U3-GPIO.3-Pad11)") (class "Default")
      (node (ref "U3") (pin "11") (pinfunction "GPIO.3_11") (pintype "bidirectional"))
    )
    (net (code "121") (name "unconnected-(U3-PAD-Pad25)") (class "Default")
      (node (ref "U3") (pin "25") (pinfunction "PAD_25") (pintype "bidirectional"))
    )
    (net (code "122") (name "unconnected-(U3-RI-Pad1)") (class "Default")
      (node (ref "U3") (pin "1") (pinfunction "RI_1") (pintype "input"))
    )
    (net (code "123") (name "unconnected-(U3-RST-Pad9)") (class "Default")
      (node (ref "U3") (pin "9") (pinfunction "RST_9") (pintype "bidirectional"))
    )
    (net (code "124") (name "unconnected-(U3-SUSPEND-Pad15)") (class "Default")
      (node (ref "U3") (pin "15") (pinfunction "SUSPEND_15") (pintype "output"))
    )
    (net (code "125") (name "unconnected-(U3-SUSPEND-Pad17)") (class "Default")
      (node (ref "U3") (pin "17") (pinfunction "SUSPEND_17") (pintype "output"))
    )
    (net (code "126") (name "unconnected-(U3-VIO{slash}NC-Pad10)") (class "Default")
      (node (ref "U3") (pin "10") (pinfunction "VIO/NC_10") (pintype "bidirectional+no_connect"))
    )
    (net (code "127") (name "unconnected-(U3-VPP-Pad16)") (class "Default")
      (node (ref "U3") (pin "16") (pinfunction "VPP_16") (pintype "unspecified"))
    )
    (net (code "128") (name "unconnected-(U6-NC-Pad5)") (class "Default")
      (node (ref "U6") (pin "5") (pinfunction "NC_5") (pintype "unspecified+no_connect"))
    )
    (net (code "129") (name "unconnected-(U6-NC-Pad6)") (class "Default")
      (node (ref "U6") (pin "6") (pinfunction "NC_6") (pintype "unspecified+no_connect"))
    )
    (net (code "130") (name "unconnected-(U15-SC3-Pad8)") (class "Default")
      (node (ref "U15") (pin "8") (pinfunction "SC3_8") (pintype "bidirectional"))
    )
    (net (code "131") (name "unconnected-(U15-SC4-Pad11)") (class "Default")
      (node (ref "U15") (pin "11") (pinfunction "SC4_11") (pintype "bidirectional"))
    )
    (net (code "132") (name "unconnected-(U15-SC5-Pad13)") (class "Default")
      (node (ref "U15") (pin "13") (pinfunction "SC5_13") (pintype "bidirectional"))
    )
    (net (code "133") (name "unconnected-(U15-SC6-Pad15)") (class "Default")
      (node (ref "U15") (pin "15") (pinfunction "SC6_15") (pintype "bidirectional"))
    )
    (net (code "134") (name "unconnected-(U15-SD3-Pad7)") (class "Default")
      (node (ref "U15") (pin "7") (pinfunction "SD3_7") (pintype "bidirectional"))
    )
    (net (code "135") (name "unconnected-(U15-SD4-Pad10)") (class "Default")
      (node (ref "U15") (pin "10") (pinfunction "SD4_10") (pintype "bidirectional"))
    )
    (net (code "136") (name "unconnected-(U15-SD5-Pad12)") (class "Default")
      (node (ref "U15") (pin "12") (pinfunction "SD5_12") (pintype "bidirectional"))
    )
    (net (code "137") (name "unconnected-(U15-SD6-Pad14)") (class "Default")
      (node (ref "U15") (pin "14") (pinfunction "SD6_14") (pintype "bidirectional"))
    )
    (net (code "138") (name "unconnected-(USB1-ID-Pad4)") (class "Default")
      (node (ref "USB1") (pin "4") (pinfunction "ID_4") (pintype "input"))
    )
    (net (code "139") (name "unconnected-(USB1-MTN1-Pad0)") (class "Default")
      (node (ref "USB1") (pin "0") (pinfunction "MTN1_0") (pintype "input+no_connect"))
    )
    (net (code "140") (name "unconnected-(USB1-MTN2-Pad0)") (class "Default")
      (node (ref "USB1") (pin "0") (pinfunction "MTN2_0") (pintype "input+no_connect"))
    )
    (net (code "141") (name "unconnected-(USB1-MTN3-Pad0)") (class "Default")
      (node (ref "USB1") (pin "0") (pinfunction "MTN3_0") (pintype "input+no_connect"))
    )
    (net (code "142") (name "unconnected-(USB1-MTN4-Pad0)") (class "Default")
      (node (ref "USB1") (pin "0") (pinfunction "MTN4_0") (pintype "input+no_connect"))
    )
  )
)
